# schematic.net
KiCad netlist of a schematic drawn in EAGLE
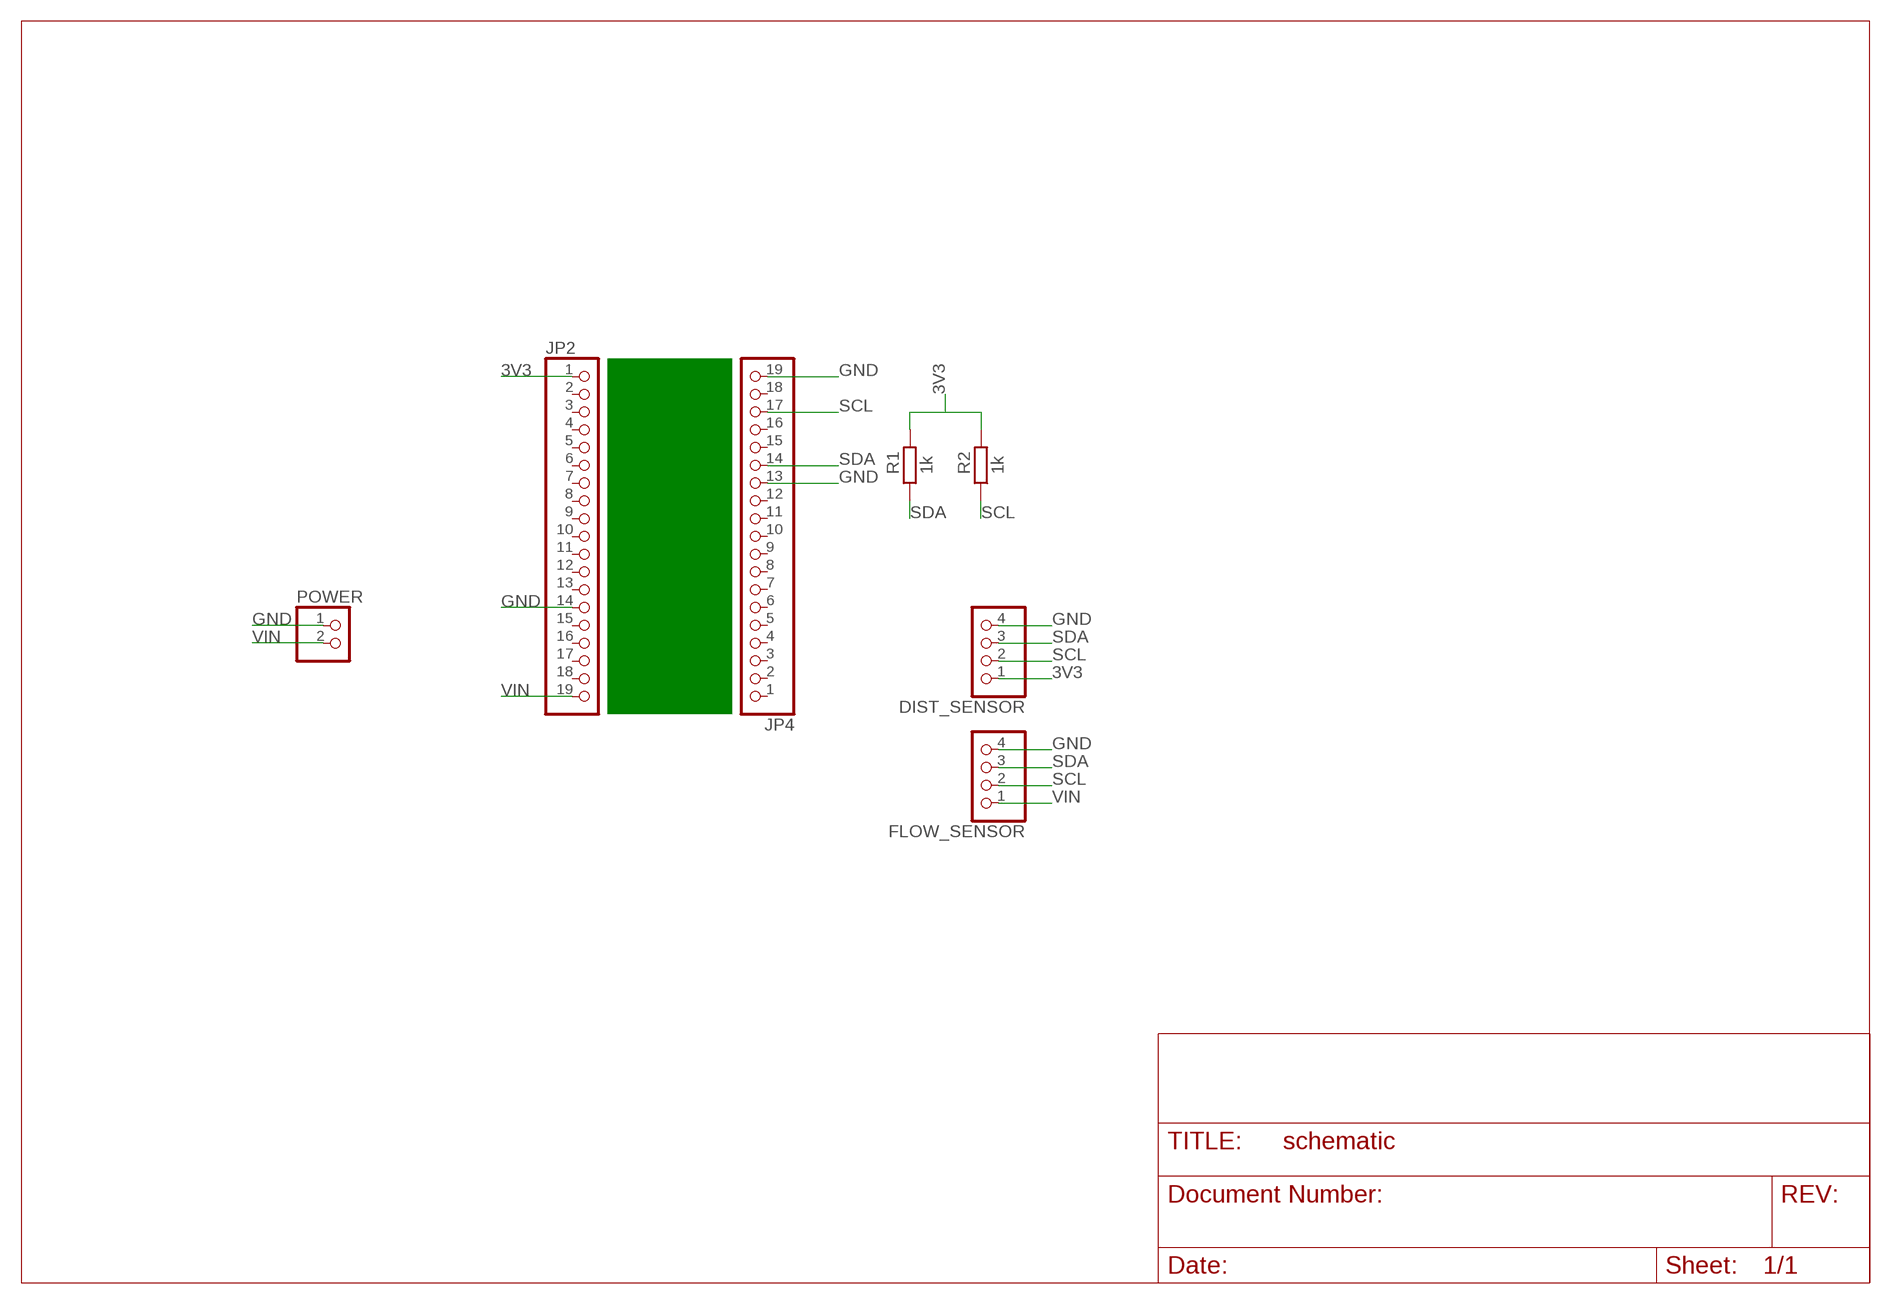
[diagram p0: schematic, sheet 1]

(export (version "E")
  (design (tool "Eeschema 10.0.6"))
  (components
    (comp (ref "DIST_SENSOR")
      (value "PINHD-1X4")
      (footprint "eagle-import:1X04")
      (libsource (lib "eagle-import") (part "PINHD-1X4"))
    )
    (comp (ref "FLOW_SENSOR")
      (value "PINHD-1X4")
      (footprint "eagle-import:1X04")
      (libsource (lib "eagle-import") (part "PINHD-1X4"))
    )
    (comp (ref "JP2")
      (value "PINHD-1X19")
      (footprint "eagle-import:1X19")
      (libsource (lib "eagle-import") (part "PINHD-1X19"))
    )
    (comp (ref "JP4")
      (value "PINHD-1X19")
      (footprint "eagle-import:1X19")
      (libsource (lib "eagle-import") (part "PINHD-1X19"))
    )
    (comp (ref "POWER")
      (value "PINHD-1X2")
      (footprint "eagle-import:1X02")
      (libsource (lib "eagle-import") (part "PINHD-1X2"))
    )
    (comp (ref "R1")
      (value "1k")
      (footprint "eagle-import:0207_10")
      (libsource (lib "eagle-import") (part "R-EU_0207/10"))
    )
    (comp (ref "R2")
      (value "1k")
      (footprint "eagle-import:0207_10")
      (libsource (lib "eagle-import") (part "R-EU_0207/10"))
    )
  )
  (nets
    (net (code "1") (name "/3V3") (class "Default")
      (node (ref "DIST_SENSOR") (pin "1") (pinfunction "1_1") (pintype "passive"))
      (node (ref "JP2") (pin "1") (pinfunction "1_1") (pintype "passive"))
      (node (ref "R1") (pin "2") (pinfunction "2_2") (pintype "passive"))
      (node (ref "R2") (pin "2") (pinfunction "2_2") (pintype "passive"))
    )
    (net (code "2") (name "/GND") (class "Default")
      (node (ref "DIST_SENSOR") (pin "4") (pinfunction "4_4") (pintype "passive"))
      (node (ref "FLOW_SENSOR") (pin "4") (pinfunction "4_4") (pintype "passive"))
      (node (ref "JP2") (pin "14") (pinfunction "14_14") (pintype "passive"))
      (node (ref "JP4") (pin "13") (pinfunction "13_13") (pintype "passive"))
      (node (ref "JP4") (pin "19") (pinfunction "19_19") (pintype "passive"))
      (node (ref "POWER") (pin "1") (pinfunction "1_1") (pintype "passive"))
    )
    (net (code "3") (name "/SCL") (class "Default")
      (node (ref "DIST_SENSOR") (pin "3") (pinfunction "3_3") (pintype "passive"))
      (node (ref "FLOW_SENSOR") (pin "3") (pinfunction "3_3") (pintype "passive"))
      (node (ref "JP4") (pin "17") (pinfunction "17_17") (pintype "passive"))
      (node (ref "R2") (pin "1") (pinfunction "1_1") (pintype "passive"))
    )
    (net (code "4") (name "/SDA") (class "Default")
      (node (ref "DIST_SENSOR") (pin "2") (pinfunction "2_2") (pintype "passive"))
      (node (ref "FLOW_SENSOR") (pin "2") (pinfunction "2_2") (pintype "passive"))
      (node (ref "JP4") (pin "14") (pinfunction "14_14") (pintype "passive"))
      (node (ref "R1") (pin "1") (pinfunction "1_1") (pintype "passive"))
    )
    (net (code "5") (name "/VIN") (class "Default")
      (node (ref "FLOW_SENSOR") (pin "1") (pinfunction "1_1") (pintype "passive"))
      (node (ref "JP2") (pin "19") (pinfunction "19_19") (pintype "passive"))
      (node (ref "POWER") (pin "2") (pinfunction "2_2") (pintype "passive"))
    )
    (net (code "6") (name "unconnected-(JP2-Pad2)") (class "Default")
      (node (ref "JP2") (pin "2") (pinfunction "2_2") (pintype "passive"))
    )
    (net (code "7") (name "unconnected-(JP2-Pad3)") (class "Default")
      (node (ref "JP2") (pin "3") (pinfunction "3_3") (pintype "passive"))
    )
    (net (code "8") (name "unconnected-(JP2-Pad4)") (class "Default")
      (node (ref "JP2") (pin "4") (pinfunction "4_4") (pintype "passive"))
    )
    (net (code "9") (name "unconnected-(JP2-Pad5)") (class "Default")
      (node (ref "JP2") (pin "5") (pinfunction "5_5") (pintype "passive"))
    )
    (net (code "10") (name "unconnected-(JP2-Pad6)") (class "Default")
      (node (ref "JP2") (pin "6") (pinfunction "6_6") (pintype "passive"))
    )
    (net (code "11") (name "unconnected-(JP2-Pad7)") (class "Default")
      (node (ref "JP2") (pin "7") (pinfunction "7_7") (pintype "passive"))
    )
    (net (code "12") (name "unconnected-(JP2-Pad8)") (class "Default")
      (node (ref "JP2") (pin "8") (pinfunction "8_8") (pintype "passive"))
    )
    (net (code "13") (name "unconnected-(JP2-Pad9)") (class "Default")
      (node (ref "JP2") (pin "9") (pinfunction "9_9") (pintype "passive"))
    )
    (net (code "14") (name "unconnected-(JP2-Pad10)") (class "Default")
      (node (ref "JP2") (pin "10") (pinfunction "10_10") (pintype "passive"))
    )
    (net (code "15") (name "unconnected-(JP2-Pad11)") (class "Default")
      (node (ref "JP2") (pin "11") (pinfunction "11_11") (pintype "passive"))
    )
    (net (code "16") (name "unconnected-(JP2-Pad12)") (class "Default")
      (node (ref "JP2") (pin "12") (pinfunction "12_12") (pintype "passive"))
    )
    (net (code "17") (name "unconnected-(JP2-Pad13)") (class "Default")
      (node (ref "JP2") (pin "13") (pinfunction "13_13") (pintype "passive"))
    )
    (net (code "18") (name "unconnected-(JP2-Pad15)") (class "Default")
      (node (ref "JP2") (pin "15") (pinfunction "15_15") (pintype "passive"))
    )
    (net (code "19") (name "unconnected-(JP2-Pad16)") (class "Default")
      (node (ref "JP2") (pin "16") (pinfunction "16_16") (pintype "passive"))
    )
    (net (code "20") (name "unconnected-(JP2-Pad17)") (class "Default")
      (node (ref "JP2") (pin "17") (pinfunction "17_17") (pintype "passive"))
    )
    (net (code "21") (name "unconnected-(JP2-Pad18)") (class "Default")
      (node (ref "JP2") (pin "18") (pinfunction "18_18") (pintype "passive"))
    )
    (net (code "22") (name "unconnected-(JP4-Pad1)") (class "Default")
      (node (ref "JP4") (pin "1") (pinfunction "1_1") (pintype "passive"))
    )
    (net (code "23") (name "unconnected-(JP4-Pad2)") (class "Default")
      (node (ref "JP4") (pin "2") (pinfunction "2_2") (pintype "passive"))
    )
    (net (code "24") (name "unconnected-(JP4-Pad3)") (class "Default")
      (node (ref "JP4") (pin "3") (pinfunction "3_3") (pintype "passive"))
    )
    (net (code "25") (name "unconnected-(JP4-Pad4)") (class "Default")
      (node (ref "JP4") (pin "4") (pinfunction "4_4") (pintype "passive"))
    )
    (net (code "26") (name "unconnected-(JP4-Pad5)") (class "Default")
      (node (ref "JP4") (pin "5") (pinfunction "5_5") (pintype "passive"))
    )
    (net (code "27") (name "unconnected-(JP4-Pad6)") (class "Default")
      (node (ref "JP4") (pin "6") (pinfunction "6_6") (pintype "passive"))
    )
    (net (code "28") (name "unconnected-(JP4-Pad7)") (class "Default")
      (node (ref "JP4") (pin "7") (pinfunction "7_7") (pintype "passive"))
    )
    (net (code "29") (name "unconnected-(JP4-Pad8)") (class "Default")
      (node (ref "JP4") (pin "8") (pinfunction "8_8") (pintype "passive"))
    )
    (net (code "30") (name "unconnected-(JP4-Pad9)") (class "Default")
      (node (ref "JP4") (pin "9") (pinfunction "9_9") (pintype "passive"))
    )
    (net (code "31") (name "unconnected-(JP4-Pad10)") (class "Default")
      (node (ref "JP4") (pin "10") (pinfunction "10_10") (pintype "passive"))
    )
    (net (code "32") (name "unconnected-(JP4-Pad11)") (class "Default")
      (node (ref "JP4") (pin "11") (pinfunction "11_11") (pintype "passive"))
    )
    (net (code "33") (name "unconnected-(JP4-Pad12)") (class "Default")
      (node (ref "JP4") (pin "12") (pinfunction "12_12") (pintype "passive"))
    )
    (net (code "34") (name "unconnected-(JP4-Pad15)") (class "Default")
      (node (ref "JP4") (pin "15") (pinfunction "15_15") (pintype "passive"))
    )
    (net (code "35") (name "unconnected-(JP4-Pad16)") (class "Default")
      (node (ref "JP4") (pin "16") (pinfunction "16_16") (pintype "passive"))
    )
    (net (code "36") (name "unconnected-(JP4-Pad18)") (class "Default")
      (node (ref "JP4") (pin "18") (pinfunction "18_18") (pintype "passive"))
    )
  )
)
